# emonTx2_5.net
KiCad netlist of a schematic drawn in EAGLE
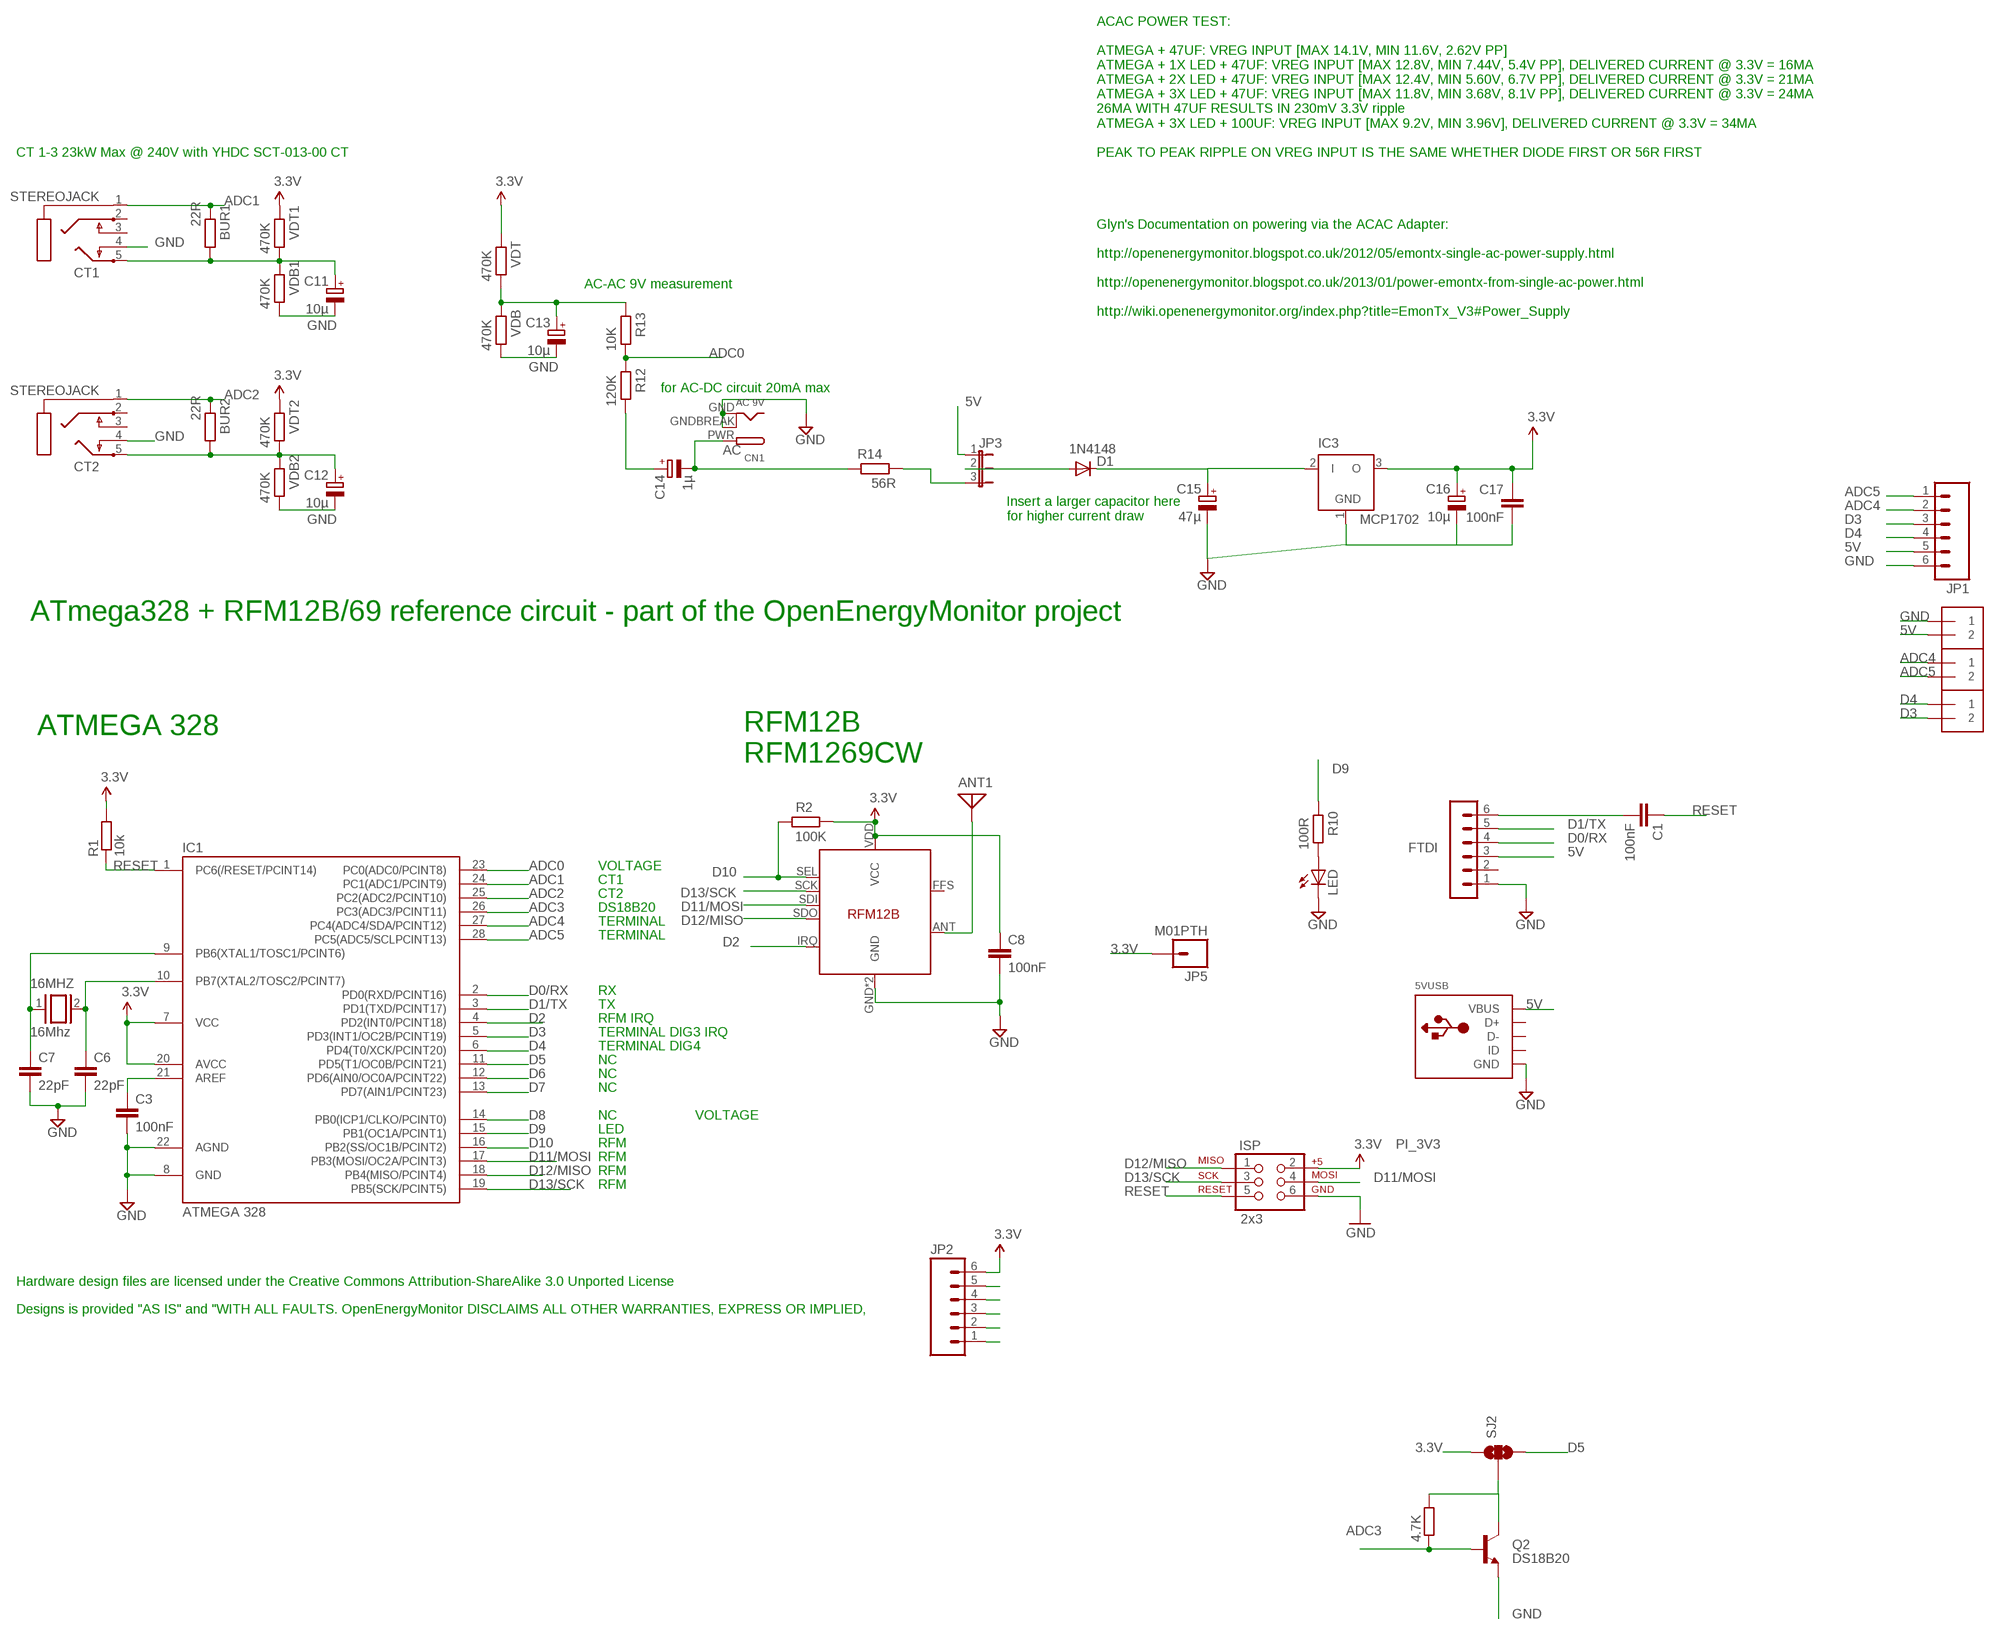
[diagram p0: schematic, sheet 1]

(export (version "E")
  (design (tool "Eeschema 10.0.6"))
  (components
    (comp (ref "5VUSB")
      (value "USBMOLEX")
      (footprint "eagle-import:USB-MINIB-THM-MOLEX")
      (libsource (lib "eagle-import") (part "USBMOLEX"))
    )
    (comp (ref "16MHZ")
      (value "16Mhz")
      (footprint "eagle-import:QS")
      (libsource (lib "eagle-import") (part "XTAL/S"))
    )
    (comp (ref "ANT1")
      (value "ANTENNA")
      (footprint "eagle-import:PAD-01")
      (libsource (lib "eagle-import") (part "ANTENNA"))
    )
    (comp (ref "BUR1")
      (value "22R")
      (footprint "eagle-import:0204_7")
      (libsource (lib "eagle-import") (part "R-EU_0204/7"))
    )
    (comp (ref "BUR2")
      (value "22R")
      (footprint "eagle-import:0204_7")
      (libsource (lib "eagle-import") (part "R-EU_0204/7"))
    )
    (comp (ref "C1")
      (value "100nF")
      (footprint "eagle-import:C025-024X044")
      (libsource (lib "eagle-import") (part "C-EU025-024X044"))
    )
    (comp (ref "C3")
      (value "100nF")
      (footprint "eagle-import:C025-024X044")
      (libsource (lib "eagle-import") (part "C-EU025-024X044"))
    )
    (comp (ref "C6")
      (value "22pF")
      (footprint "eagle-import:C2.5-2")
      (libsource (lib "eagle-import") (part "C2.5/2"))
    )
    (comp (ref "C7")
      (value "22pF")
      (footprint "eagle-import:C2.5-2")
      (libsource (lib "eagle-import") (part "C2.5/2"))
    )
    (comp (ref "C8")
      (value "100nF")
      (footprint "eagle-import:C025-024X044")
      (libsource (lib "eagle-import") (part "C-EU025-024X044"))
    )
    (comp (ref "C11")
      (value "10µ")
      (footprint "eagle-import:E1,8-4")
      (libsource (lib "eagle-import") (part "CPOL-EUE1.8-4"))
    )
    (comp (ref "C12")
      (value "10µ")
      (footprint "eagle-import:E1,8-4")
      (libsource (lib "eagle-import") (part "CPOL-EUE1.8-4"))
    )
    (comp (ref "C13")
      (value "10µ")
      (footprint "eagle-import:E1,8-4")
      (libsource (lib "eagle-import") (part "CPOL-EUE1.8-4"))
    )
    (comp (ref "C14")
      (value "1µ")
      (footprint "eagle-import:E1,8-4")
      (libsource (lib "eagle-import") (part "CPOL-EUE1.8-4"))
    )
    (comp (ref "C15")
      (value "47µ")
      (footprint "eagle-import:E1,8-4")
      (libsource (lib "eagle-import") (part "CPOL-EUE1.8-4"))
    )
    (comp (ref "C16")
      (value "10µ")
      (footprint "eagle-import:E1,8-4")
      (libsource (lib "eagle-import") (part "CPOL-EUE1.8-4"))
    )
    (comp (ref "C17")
      (value "100nF")
      (footprint "eagle-import:C025-024X044")
      (libsource (lib "eagle-import") (part "C-EU025-024X044"))
    )
    (comp (ref "CN1")
      (value "AC 9V")
      (footprint "eagle-import:DCJACK_2MM_PTH")
      (libsource (lib "eagle-import") (part "DCBARRELPTH"))
    )
    (comp (ref "CT1")
      (value "STEREOJACK")
      (footprint "eagle-import:STX3100")
      (libsource (lib "eagle-import") (part "STEREOJACK"))
    )
    (comp (ref "CT2")
      (value "STEREOJACK")
      (footprint "eagle-import:STX3100")
      (libsource (lib "eagle-import") (part "STEREOJACK"))
    )
    (comp (ref "D1")
      (value "1N4148")
      (footprint "eagle-import:DIODE-1N4148")
      (libsource (lib "eagle-import") (part "DIODE1N4148"))
    )
    (comp (ref "FTDI")
      (value "FTDI")
      (footprint "eagle-import:MA06-1")
      (libsource (lib "eagle-import") (part "MA06-1"))
    )
    (comp (ref "IC1")
      (value "ATMEGA 328")
      (footprint "eagle-import:DIL28-3")
      (libsource (lib "eagle-import") (part "ATMEGA48/88/168-PU"))
    )
    (comp (ref "IC3")
      (value "MCP1702")
      (footprint "eagle-import:TO92")
      (libsource (lib "eagle-import") (part "MCP1702Z"))
    )
    (comp (ref "ISP")
      (value "2x3")
      (footprint "eagle-import:2X3")
      (libsource (lib "eagle-import") (part "AVR_SPI_PRG_6PTH"))
    )
    (comp (ref "J1")
      (value "1X2-3.5MM")
      (footprint "eagle-import:1X2-3.5MM")
      (libsource (lib "eagle-import") (part "1X2-3.5MM"))
    )
    (comp (ref "J2")
      (value "1X2-3.5MM")
      (footprint "eagle-import:1X2-3.5MM")
      (libsource (lib "eagle-import") (part "1X2-3.5MM"))
    )
    (comp (ref "J3")
      (value "1X2-3.5MM")
      (footprint "eagle-import:1X2-3.5MM")
      (libsource (lib "eagle-import") (part "1X2-3.5MM"))
    )
    (comp (ref "JP1")
      (value "M06SIP")
      (footprint "eagle-import:1X06")
      (libsource (lib "eagle-import") (part "M06SIP"))
    )
    (comp (ref "JP2")
      (value "M06SIP")
      (footprint "eagle-import:1X06")
      (libsource (lib "eagle-import") (part "M06SIP"))
    )
    (comp (ref "JP3")
      (value "JP2E")
      (footprint "eagle-import:JP2")
      (libsource (lib "eagle-import") (part "JP2E"))
    )
    (comp (ref "JP5")
      (value "M01PTH")
      (footprint "eagle-import:1X01")
      (libsource (lib "eagle-import") (part "M01PTH"))
    )
    (comp (ref "LED")
      (value "LED3MM")
      (footprint "eagle-import:LED3MM")
      (libsource (lib "eagle-import") (part "LED3MM"))
    )
    (comp (ref "Q2")
      (value "DS18B20")
      (footprint "eagle-import:TO-92")
      (libsource (lib "eagle-import") (part "TRANSISTOR_NPNTO92"))
    )
    (comp (ref "R1")
      (value "10k")
      (footprint "eagle-import:0204_7")
      (libsource (lib "eagle-import") (part "resistor_R-EU_0204/7"))
    )
    (comp (ref "R2")
      (value "100K")
      (footprint "eagle-import:0204_7")
      (libsource (lib "eagle-import") (part "R-EU_0204/7"))
    )
    (comp (ref "R9")
      (value "4.7K")
      (footprint "eagle-import:0204_7")
      (libsource (lib "eagle-import") (part "R-EU_0204/7"))
    )
    (comp (ref "R10")
      (value "100R")
      (footprint "eagle-import:0204_7")
      (libsource (lib "eagle-import") (part "R-EU_0204/7"))
    )
    (comp (ref "R12")
      (value "120K")
      (footprint "eagle-import:0204_7")
      (libsource (lib "eagle-import") (part "R-EU_0204/7"))
    )
    (comp (ref "R13")
      (value "10K")
      (footprint "eagle-import:0204_7")
      (libsource (lib "eagle-import") (part "R-EU_0204/7"))
    )
    (comp (ref "R14")
      (value "56R")
      (footprint "eagle-import:0204_7")
      (libsource (lib "eagle-import") (part "R-EU_0204/7"))
    )
    (comp (ref "SJ2")
      (value "SOLDERJUMPER_2WAY-OLDS")
      (footprint "eagle-import:SJ_3")
      (libsource (lib "eagle-import") (part "SOLDERJUMPER_2WAY-OLDS"))
    )
    (comp (ref "U$14")
      (value "RFM12B")
      (footprint "eagle-import:RFM12B")
      (libsource (lib "eagle-import") (part "RFM12B"))
    )
    (comp (ref "VDB")
      (value "470K")
      (footprint "eagle-import:0204_7")
      (libsource (lib "eagle-import") (part "R-EU_0204/7"))
    )
    (comp (ref "VDB1")
      (value "470K")
      (footprint "eagle-import:0204_7")
      (libsource (lib "eagle-import") (part "R-EU_0204/7"))
    )
    (comp (ref "VDB2")
      (value "470K")
      (footprint "eagle-import:0204_7")
      (libsource (lib "eagle-import") (part "R-EU_0204/7"))
    )
    (comp (ref "VDT")
      (value "470K")
      (footprint "eagle-import:0204_7")
      (libsource (lib "eagle-import") (part "R-EU_0204/7"))
    )
    (comp (ref "VDT1")
      (value "470K")
      (footprint "eagle-import:0204_7")
      (libsource (lib "eagle-import") (part "R-EU_0204/7"))
    )
    (comp (ref "VDT2")
      (value "470K")
      (footprint "eagle-import:0204_7")
      (libsource (lib "eagle-import") (part "R-EU_0204/7"))
    )
  )
  (nets
    (net (code "1") (name "/5V") (class "Default")
      (node (ref "5VUSB") (pin "VBUS") (pinfunction "VBUS_VBUS") (pintype "power_in"))
      (node (ref "FTDI") (pin "3") (pinfunction "3_3") (pintype "passive"))
      (node (ref "J3") (pin "2") (pinfunction "2_2") (pintype "passive"))
      (node (ref "JP1") (pin "5") (pinfunction "5_5") (pintype "passive"))
      (node (ref "JP3") (pin "1") (pinfunction "1_1") (pintype "passive"))
    )
    (net (code "2") (name "/AC") (class "Default")
      (node (ref "C14") (pin "-") (pinfunction "-_-") (pintype "passive"))
      (node (ref "CN1") (pin "PWR") (pinfunction "PWR_PWR") (pintype "power_in"))
      (node (ref "R14") (pin "2") (pinfunction "2_2") (pintype "passive"))
    )
    (net (code "3") (name "/ADC0") (class "Default")
      (node (ref "IC1") (pin "23") (pinfunction "PC0(ADC0/PCINT8)_23") (pintype "bidirectional"))
      (node (ref "R12") (pin "2") (pinfunction "2_2") (pintype "passive"))
      (node (ref "R13") (pin "1") (pinfunction "1_1") (pintype "passive"))
    )
    (net (code "4") (name "/ADC1") (class "Default")
      (node (ref "BUR1") (pin "2") (pinfunction "2_2") (pintype "passive"))
      (node (ref "CT1") (pin "1") (pinfunction "1_1") (pintype "passive"))
      (node (ref "IC1") (pin "24") (pinfunction "PC1(ADC1/PCINT9)_24") (pintype "bidirectional"))
    )
    (net (code "5") (name "/ADC2") (class "Default")
      (node (ref "BUR2") (pin "2") (pinfunction "2_2") (pintype "passive"))
      (node (ref "CT2") (pin "1") (pinfunction "1_1") (pintype "passive"))
      (node (ref "IC1") (pin "25") (pinfunction "PC2(ADC2/PCINT10)_25") (pintype "bidirectional"))
    )
    (net (code "6") (name "/ADC3") (class "Default")
      (node (ref "IC1") (pin "26") (pinfunction "PC3(ADC3/PCINT11)_26") (pintype "bidirectional"))
      (node (ref "Q2") (pin "2") (pinfunction "B_2") (pintype "passive"))
      (node (ref "R9") (pin "2") (pinfunction "2_2") (pintype "passive"))
    )
    (net (code "7") (name "/ADC4") (class "Default")
      (node (ref "IC1") (pin "27") (pinfunction "PC4(ADC4/SDA/PCINT12)_27") (pintype "bidirectional"))
      (node (ref "J1") (pin "1") (pinfunction "1_1") (pintype "passive"))
      (node (ref "JP1") (pin "2") (pinfunction "2_2") (pintype "passive"))
    )
    (net (code "8") (name "/ADC5") (class "Default")
      (node (ref "IC1") (pin "28") (pinfunction "PC5(ADC5/SCLPCINT13)_28") (pintype "bidirectional"))
      (node (ref "J1") (pin "2") (pinfunction "2_2") (pintype "passive"))
      (node (ref "JP1") (pin "1") (pinfunction "1_1") (pintype "passive"))
    )
    (net (code "9") (name "/D0{slash}RX") (class "Default")
      (node (ref "FTDI") (pin "4") (pinfunction "4_4") (pintype "passive"))
      (node (ref "IC1") (pin "2") (pinfunction "PD0(RXD/PCINT16)_2") (pintype "bidirectional"))
    )
    (net (code "10") (name "/D1{slash}TX") (class "Default")
      (node (ref "FTDI") (pin "5") (pinfunction "5_5") (pintype "passive"))
      (node (ref "IC1") (pin "3") (pinfunction "PD1(TXD/PCINT17)_3") (pintype "bidirectional"))
    )
    (net (code "11") (name "/D2") (class "Default")
      (node (ref "IC1") (pin "4") (pinfunction "PD2(INT0/PCINT18)_4") (pintype "bidirectional"))
      (node (ref "U$14") (pin "IRQ") (pinfunction "IRQ_IRQ") (pintype "open_collector"))
    )
    (net (code "12") (name "/D3") (class "Default")
      (node (ref "IC1") (pin "5") (pinfunction "PD3(INT1/OC2B/PCINT19)_5") (pintype "bidirectional"))
      (node (ref "J2") (pin "2") (pinfunction "2_2") (pintype "passive"))
      (node (ref "JP1") (pin "3") (pinfunction "3_3") (pintype "passive"))
    )
    (net (code "13") (name "/D4") (class "Default")
      (node (ref "IC1") (pin "6") (pinfunction "PD4(T0/XCK/PCINT20)_6") (pintype "bidirectional"))
      (node (ref "J2") (pin "1") (pinfunction "1_1") (pintype "passive"))
      (node (ref "JP1") (pin "4") (pinfunction "4_4") (pintype "passive"))
    )
    (net (code "14") (name "/D5") (class "Default")
      (node (ref "IC1") (pin "11") (pinfunction "PD5(T1/OC0B/PCINT21)_11") (pintype "bidirectional"))
      (node (ref "JP2") (pin "2") (pinfunction "2_2") (pintype "passive"))
      (node (ref "SJ2") (pin "3") (pinfunction "3_3") (pintype "passive"))
    )
    (net (code "15") (name "/D6") (class "Default")
      (node (ref "IC1") (pin "12") (pinfunction "PD6(AIN0/OC0A/PCINT22)_12") (pintype "bidirectional"))
      (node (ref "JP2") (pin "3") (pinfunction "3_3") (pintype "passive"))
    )
    (net (code "16") (name "/D7") (class "Default")
      (node (ref "IC1") (pin "13") (pinfunction "PD7(AIN1/PCINT23)_13") (pintype "bidirectional"))
      (node (ref "JP2") (pin "4") (pinfunction "4_4") (pintype "passive"))
    )
    (net (code "17") (name "/D8") (class "Default")
      (node (ref "IC1") (pin "14") (pinfunction "PB0(ICP1/CLKO/PCINT0)_14") (pintype "bidirectional"))
      (node (ref "JP2") (pin "5") (pinfunction "5_5") (pintype "passive"))
    )
    (net (code "18") (name "/D9") (class "Default")
      (node (ref "IC1") (pin "15") (pinfunction "PB1(OC1A/PCINT1)_15") (pintype "bidirectional"))
      (node (ref "R10") (pin "2") (pinfunction "2_2") (pintype "passive"))
    )
    (net (code "19") (name "/D10") (class "Default")
      (node (ref "IC1") (pin "16") (pinfunction "PB2(SS/OC1B/PCINT2)_16") (pintype "bidirectional"))
      (node (ref "R2") (pin "2") (pinfunction "2_2") (pintype "passive"))
      (node (ref "U$14") (pin "SEL") (pinfunction "SEL_SEL") (pintype "input"))
    )
    (net (code "20") (name "/D11{slash}MOSI") (class "Default")
      (node (ref "IC1") (pin "17") (pinfunction "PB3(MOSI/OC2A/PCINT3)_17") (pintype "bidirectional"))
      (node (ref "ISP") (pin "4") (pinfunction "4_4") (pintype "passive"))
      (node (ref "U$14") (pin "SDI") (pinfunction "SDI_SDI") (pintype "input"))
    )
    (net (code "21") (name "/D12{slash}MISO") (class "Default")
      (node (ref "IC1") (pin "18") (pinfunction "PB4(MISO/PCINT4)_18") (pintype "bidirectional"))
      (node (ref "ISP") (pin "1") (pinfunction "1_1") (pintype "passive"))
      (node (ref "U$14") (pin "SDO") (pinfunction "SDO_SDO") (pintype "output"))
    )
    (net (code "22") (name "/D13{slash}SCK") (class "Default")
      (node (ref "IC1") (pin "19") (pinfunction "PB5(SCK/PCINT5)_19") (pintype "bidirectional"))
      (node (ref "ISP") (pin "3") (pinfunction "3_3") (pintype "passive"))
      (node (ref "U$14") (pin "SCK") (pinfunction "SCK_SCK") (pintype "input"))
    )
    (net (code "24") (name "/RESET") (class "Default")
      (node (ref "C1") (pin "1") (pinfunction "1_1") (pintype "passive"))
      (node (ref "IC1") (pin "1") (pinfunction "PC6(/RESET/PCINT14)_1") (pintype "bidirectional"))
      (node (ref "ISP") (pin "5") (pinfunction "5_5") (pintype "passive"))
      (node (ref "R1") (pin "1") (pinfunction "1_1") (pintype "passive"))
    )
    (net (code "25") (name "3.3V") (class "Default")
      (node (ref "C16") (pin "+") (pinfunction "+_+") (pintype "passive"))
      (node (ref "C17") (pin "1") (pinfunction "1_1") (pintype "passive"))
      (node (ref "C8") (pin "1") (pinfunction "1_1") (pintype "passive"))
      (node (ref "IC1") (pin "20") (pinfunction "AVCC_20") (pintype "passive"))
      (node (ref "IC1") (pin "7") (pinfunction "VCC_7") (pintype "power_in"))
      (node (ref "IC3") (pin "3") (pinfunction "O_3") (pintype "input"))
      (node (ref "ISP") (pin "2") (pinfunction "2_2") (pintype "passive"))
      (node (ref "JP2") (pin "6") (pinfunction "6_6") (pintype "passive"))
      (node (ref "JP5") (pin "1") (pinfunction "1_1") (pintype "passive"))
      (node (ref "R1") (pin "2") (pinfunction "2_2") (pintype "passive"))
      (node (ref "R2") (pin "1") (pinfunction "1_1") (pintype "passive"))
      (node (ref "SJ2") (pin "1") (pinfunction "1_1") (pintype "passive"))
      (node (ref "U$14") (pin "VDD") (pinfunction "VCC_VDD") (pintype "power_in"))
      (node (ref "VDT") (pin "2") (pinfunction "2_2") (pintype "passive"))
      (node (ref "VDT1") (pin "2") (pinfunction "2_2") (pintype "passive"))
      (node (ref "VDT2") (pin "2") (pinfunction "2_2") (pintype "passive"))
    )
    (net (code "26") (name "GND") (class "Default")
      (node (ref "5VUSB") (pin "GND") (pinfunction "GND_GND") (pintype "power_in"))
      (node (ref "C11") (pin "-") (pinfunction "-_-") (pintype "passive"))
      (node (ref "C12") (pin "-") (pinfunction "-_-") (pintype "passive"))
      (node (ref "C13") (pin "-") (pinfunction "-_-") (pintype "passive"))
      (node (ref "C15") (pin "-") (pinfunction "-_-") (pintype "passive"))
      (node (ref "C16") (pin "-") (pinfunction "-_-") (pintype "passive"))
      (node (ref "C17") (pin "2") (pinfunction "2_2") (pintype "passive"))
      (node (ref "C3") (pin "2") (pinfunction "2_2") (pintype "passive"))
      (node (ref "C6") (pin "2") (pinfunction "2_2") (pintype "passive"))
      (node (ref "C7") (pin "2") (pinfunction "2_2") (pintype "passive"))
      (node (ref "C8") (pin "2") (pinfunction "2_2") (pintype "passive"))
      (node (ref "CN1") (pin "GND") (pinfunction "GND_GND") (pintype "power_in"))
      (node (ref "CN1") (pin "GNDBREAK") (pinfunction "GNDBREAK_GNDBREAK") (pintype "power_in"))
      (node (ref "CT1") (pin "4") (pinfunction "4_4") (pintype "passive"))
      (node (ref "CT2") (pin "4") (pinfunction "4_4") (pintype "passive"))
      (node (ref "FTDI") (pin "1") (pinfunction "1_1") (pintype "passive"))
      (node (ref "IC1") (pin "22") (pinfunction "AGND_22") (pintype "power_in"))
      (node (ref "IC1") (pin "8") (pinfunction "GND_8") (pintype "power_in"))
      (node (ref "IC3") (pin "1") (pinfunction "GND_1") (pintype "power_in"))
      (node (ref "ISP") (pin "6") (pinfunction "6_6") (pintype "passive"))
      (node (ref "J3") (pin "1") (pinfunction "1_1") (pintype "passive"))
      (node (ref "JP1") (pin "6") (pinfunction "6_6") (pintype "passive"))
      (node (ref "JP2") (pin "1") (pinfunction "1_1") (pintype "passive"))
      (node (ref "LED") (pin "K") (pinfunction "C_K") (pintype "passive"))
      (node (ref "Q2") (pin "1") (pinfunction "E_1") (pintype "passive"))
      (node (ref "U$14") (pin "GND") (pinfunction "GND_GND") (pintype "power_in"))
      (node (ref "U$14") (pin "P$12") (pinfunction "GND_P$12") (pintype "power_in"))
      (node (ref "VDB") (pin "1") (pinfunction "1_1") (pintype "passive"))
      (node (ref "VDB1") (pin "1") (pinfunction "1_1") (pintype "passive"))
      (node (ref "VDB2") (pin "1") (pinfunction "1_1") (pintype "passive"))
    )
    (net (code "27") (name "Net-(ANT1-Pad1)") (class "Default")
      (node (ref "ANT1") (pin "1") (pinfunction "1_1") (pintype "output"))
      (node (ref "U$14") (pin "ANT") (pinfunction "ANT_ANT") (pintype "passive"))
    )
    (net (code "28") (name "Net-(BUR1-Pad1)") (class "Default")
      (node (ref "BUR1") (pin "1") (pinfunction "1_1") (pintype "passive"))
      (node (ref "C11") (pin "+") (pinfunction "+_+") (pintype "passive"))
      (node (ref "CT1") (pin "5") (pinfunction "5_5") (pintype "passive"))
      (node (ref "VDB1") (pin "2") (pinfunction "2_2") (pintype "passive"))
      (node (ref "VDT1") (pin "1") (pinfunction "1_1") (pintype "passive"))
    )
    (net (code "29") (name "Net-(BUR2-Pad1)") (class "Default")
      (node (ref "BUR2") (pin "1") (pinfunction "1_1") (pintype "passive"))
      (node (ref "C12") (pin "+") (pinfunction "+_+") (pintype "passive"))
      (node (ref "CT2") (pin "5") (pinfunction "5_5") (pintype "passive"))
      (node (ref "VDB2") (pin "2") (pinfunction "2_2") (pintype "passive"))
      (node (ref "VDT2") (pin "1") (pinfunction "1_1") (pintype "passive"))
    )
    (net (code "30") (name "Net-(C1-Pad2)") (class "Default")
      (node (ref "C1") (pin "2") (pinfunction "2_2") (pintype "passive"))
      (node (ref "FTDI") (pin "6") (pinfunction "6_6") (pintype "passive"))
    )
    (net (code "31") (name "Net-(C13-Pad+)") (class "Default")
      (node (ref "C13") (pin "+") (pinfunction "+_+") (pintype "passive"))
      (node (ref "R13") (pin "2") (pinfunction "2_2") (pintype "passive"))
      (node (ref "VDB") (pin "2") (pinfunction "2_2") (pintype "passive"))
      (node (ref "VDT") (pin "1") (pinfunction "1_1") (pintype "passive"))
    )
    (net (code "32") (name "Net-(C14-Pad+)") (class "Default")
      (node (ref "C14") (pin "+") (pinfunction "+_+") (pintype "passive"))
      (node (ref "R12") (pin "1") (pinfunction "1_1") (pintype "passive"))
    )
    (net (code "33") (name "Net-(D1-PadA)") (class "Default")
      (node (ref "D1") (pin "A") (pinfunction "A_A") (pintype "passive"))
      (node (ref "JP3") (pin "2") (pinfunction "2_2") (pintype "passive"))
    )
    (net (code "34") (name "Net-(IC1-AREF)") (class "Default")
      (node (ref "C3") (pin "1") (pinfunction "1_1") (pintype "passive"))
      (node (ref "IC1") (pin "21") (pinfunction "AREF_21") (pintype "passive"))
    )
    (net (code "35") (name "Net-(IC1-PB6(XTAL1{slash}TOSC1{slash}PCINT6))") (class "Default")
      (node (ref "16MHZ") (pin "1") (pinfunction "1_1") (pintype "passive"))
      (node (ref "C7") (pin "1") (pinfunction "1_1") (pintype "passive"))
      (node (ref "IC1") (pin "9") (pinfunction "PB6(XTAL1/TOSC1/PCINT6)_9") (pintype "bidirectional"))
    )
    (net (code "36") (name "Net-(IC1-PB7(XTAL2{slash}TOSC2{slash}PCINT7))") (class "Default")
      (node (ref "16MHZ") (pin "2") (pinfunction "2_2") (pintype "passive"))
      (node (ref "C6") (pin "1") (pinfunction "1_1") (pintype "passive"))
      (node (ref "IC1") (pin "10") (pinfunction "PB7(XTAL2/TOSC2/PCINT7)_10") (pintype "bidirectional"))
    )
    (net (code "37") (name "Net-(IC3-I)") (class "Default")
      (node (ref "C15") (pin "+") (pinfunction "+_+") (pintype "passive"))
      (node (ref "D1") (pin "C") (pinfunction "C_C") (pintype "passive"))
      (node (ref "IC3") (pin "2") (pinfunction "I_2") (pintype "input"))
    )
    (net (code "38") (name "Net-(JP3-Pad3)") (class "Default")
      (node (ref "JP3") (pin "3") (pinfunction "3_3") (pintype "passive"))
      (node (ref "R14") (pin "1") (pinfunction "1_1") (pintype "passive"))
    )
    (net (code "39") (name "Net-(LED-PadA)") (class "Default")
      (node (ref "LED") (pin "A") (pinfunction "A_A") (pintype "passive"))
      (node (ref "R10") (pin "1") (pinfunction "1_1") (pintype "passive"))
    )
    (net (code "40") (name "Net-(Q2-C)") (class "Default")
      (node (ref "Q2") (pin "3") (pinfunction "C_3") (pintype "passive"))
      (node (ref "R9") (pin "1") (pinfunction "1_1") (pintype "passive"))
      (node (ref "SJ2") (pin "2") (pinfunction "2_2") (pintype "passive"))
    )
    (net (code "41") (name "unconnected-(5VUSB-PadD+)") (class "Default")
      (node (ref "5VUSB") (pin "D+") (pinfunction "D+_D+") (pintype "bidirectional"))
    )
    (net (code "42") (name "unconnected-(5VUSB-PadD-)") (class "Default")
      (node (ref "5VUSB") (pin "D-") (pinfunction "D-_D-") (pintype "bidirectional"))
    )
    (net (code "43") (name "unconnected-(5VUSB-PadID)") (class "Default")
      (node (ref "5VUSB") (pin "ID") (pinfunction "ID_ID") (pintype "bidirectional"))
    )
    (net (code "44") (name "unconnected-(CT1-Pad2)") (class "Default")
      (node (ref "CT1") (pin "2") (pinfunction "2_2") (pintype "passive"))
    )
    (net (code "45") (name "unconnected-(CT1-Pad3)") (class "Default")
      (node (ref "CT1") (pin "3") (pinfunction "3_3") (pintype "passive"))
    )
    (net (code "46") (name "unconnected-(CT2-Pad2)") (class "Default")
      (node (ref "CT2") (pin "2") (pinfunction "2_2") (pintype "passive"))
    )
    (net (code "47") (name "unconnected-(CT2-Pad3)") (class "Default")
      (node (ref "CT2") (pin "3") (pinfunction "3_3") (pintype "passive"))
    )
    (net (code "48") (name "unconnected-(FTDI-Pad2)") (class "Default")
      (node (ref "FTDI") (pin "2") (pinfunction "2_2") (pintype "passive"))
    )
    (net (code "49") (name "unconnected-(U$14-PadFFS)") (class "Default")
      (node (ref "U$14") (pin "FFS") (pinfunction "FFS_FFS") (pintype "bidirectional"))
    )
  )
)
